# PROC051C_QSPI_Flash_Reference.net
KiCad netlist of a schematic drawn in Altium Designer
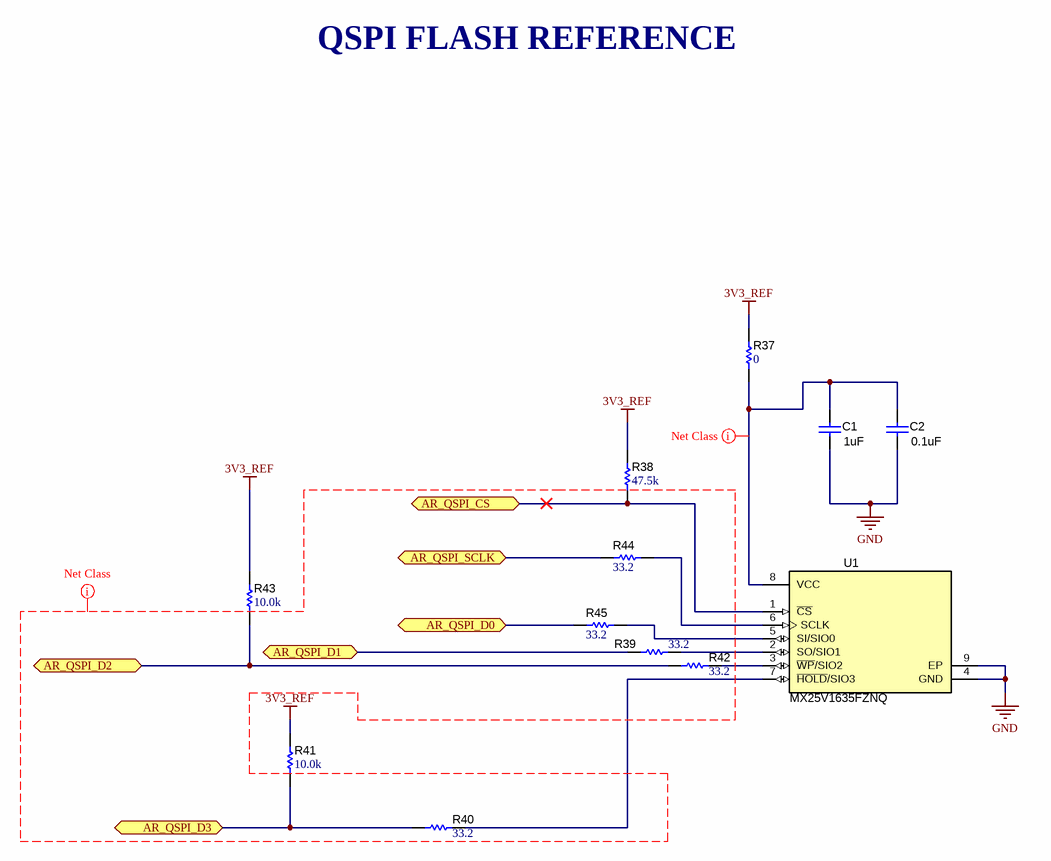
[diagram p0: PROC051C_QSPI_Flash_Reference.SchDoc]

(export (version "E")
  (design (tool "Eeschema 10.0.6"))
  (components
    (comp (ref "C1")
      (value "GCM188R71C105KA64D")
      (footprint "0603")
      (description "CAP, CERM, 1 uF, 16 V, +/- 10%, X7R, AEC-Q200 Grade 1, 0603")
      (fields
        (field (name "MANUFACTURER") "MuRata")
        (field (name "VALUEDISPLAYED") "1uF")
        (field (name "PUBLISHER") "Texas Instruments")
      )
      (libsource (lib "Altium Vault - TI") (part "Capacitor"))
    )
    (comp (ref "C2")
      (value "CGA2B3X7R1H104K050BB")
      (footprint "0402L")
      (description "CAP, CERM, 0.1 uF, 50 V, +/- 10%, X7R, AEC-Q200 Grade 1, 0402")
      (fields
        (field (name "MANUFACTURER") "TDK")
        (field (name "VALUEDISPLAYED") "0.1uF")
        (field (name "PUBLISHER") "Texas Instruments")
      )
      (libsource (lib "Altium Vault - TI") (part "Capacitor"))
    )
    (comp (ref "R37")
      (value "ERJ-2GE0R00X")
      (footprint "0402L")
      (description "RES, 0, 5%, 0.1 W, AEC-Q200 Grade 0, 0402")
      (fields (field (name "MANUFACTURER") "Panasonic") (field (name "VALUEDISPLAYED") "0"))
      (libsource (lib "Altium Vault - TI") (part "Resistor"))
    )
    (comp (ref "R38")
      (value "CRCW040247K5FKED")
      (footprint "0402L")
      (description "RES, 47.5 k, 1%, 0.063 W, AEC-Q200 Grade 0, 0402")
      (fields (field (name "MANUFACTURER") "Vishay-Dale") (field (name "VALUEDISPLAYED") "47.5k"))
      (libsource (lib "Altium Vault - TI") (part "Resistor"))
    )
    (comp (ref "R39")
      (value "CRCW020133R2FNED")
      (footprint "0201_Silk")
      (description "RES, 33.2, 1%, 0.05 W, 0201")
      (fields (field (name "MANUFACTURER") "Vishay-Dale") (field (name "VALUEDISPLAYED") "33.2"))
      (libsource (lib "Altium Vault - TI") (part "Resistor"))
    )
    (comp (ref "R40")
      (value "CRCW020133R2FNED")
      (footprint "0201_Silk")
      (description "RES, 33.2, 1%, 0.05 W, 0201")
      (fields (field (name "MANUFACTURER") "Vishay-Dale") (field (name "VALUEDISPLAYED") "33.2"))
      (libsource (lib "Altium Vault - TI") (part "Resistor"))
    )
    (comp (ref "R41")
      (value "CRCW040210K0FKED")
      (footprint "0402L")
      (description "RES, 10.0 k, 1%, 0.063 W, AEC-Q200 Grade 0, 0402")
      (fields (field (name "MANUFACTURER") "Vishay-Dale") (field (name "VALUEDISPLAYED") "10.0k"))
      (libsource (lib "Altium Vault - TI") (part "Resistor"))
    )
    (comp (ref "R42")
      (value "CRCW020133R2FNED")
      (footprint "0201_Silk")
      (description "RES, 33.2, 1%, 0.05 W, 0201")
      (fields (field (name "MANUFACTURER") "Vishay-Dale") (field (name "VALUEDISPLAYED") "33.2"))
      (libsource (lib "Altium Vault - TI") (part "Resistor"))
    )
    (comp (ref "R43")
      (value "CRCW040210K0FKED")
      (footprint "0402L")
      (description "RES, 10.0 k, 1%, 0.063 W, AEC-Q200 Grade 0, 0402")
      (fields (field (name "MANUFACTURER") "Vishay-Dale") (field (name "VALUEDISPLAYED") "10.0k"))
      (libsource (lib "Altium Vault - TI") (part "Resistor"))
    )
    (comp (ref "R44")
      (value "CRCW020133R2FNED")
      (footprint "0201_Silk")
      (description "RES, 33.2, 1%, 0.05 W, 0201")
      (fields (field (name "MANUFACTURER") "Vishay-Dale") (field (name "VALUEDISPLAYED") "33.2"))
      (libsource (lib "Altium Vault - TI") (part "CMP-0027275-3"))
    )
    (comp (ref "R45")
      (value "CRCW020133R2FNED")
      (footprint "0201_Silk")
      (description "RES, 33.2, 1%, 0.05 W, 0201")
      (fields (field (name "MANUFACTURER") "Vishay-Dale") (field (name "VALUEDISPLAYED") "33.2"))
      (libsource (lib "Altium Vault - TI") (part "Resistor"))
    )
    (comp (ref "U1")
      (value "MX25V1635FZNQ")
      (footprint "WSON-8L_6x5MM_EP")
      (description "2.3V-3.6V, 16M-BIT [x 1/x 2/x 4] CMOS FLASH Memory, WSON-8")
      (fields (field (name "MANUFACTURER") "Macronix International Co., LTD"))
      (libsource (lib "Altium Vault - TI") (part "MX25V1635FZ"))
    )
  )
  (nets
    (net (code "1") (name "/AR_QSPI_CS") (class "Default")
      (node (ref "R38") (pin "1") (pinfunction "1_1") (pintype "passive"))
      (node (ref "U1") (pin "1") (pinfunction "CS_1") (pintype "input"))
    )
    (net (code "2") (name "/AR_QSPI_D0") (class "Default")
      (node (ref "R45") (pin "2") (pinfunction "2_2") (pintype "passive"))
    )
    (net (code "3") (name "/AR_QSPI_D1") (class "Default")
      (node (ref "R39") (pin "1") (pinfunction "1_1") (pintype "passive"))
    )
    (net (code "4") (name "/AR_QSPI_D2") (class "Default")
      (node (ref "R42") (pin "1") (pinfunction "1_1") (pintype "passive"))
      (node (ref "R43") (pin "1") (pinfunction "1_1") (pintype "passive"))
    )
    (net (code "5") (name "/AR_QSPI_D3") (class "Default")
      (node (ref "R40") (pin "2") (pinfunction "2_2") (pintype "passive"))
      (node (ref "R41") (pin "1") (pinfunction "1_1") (pintype "passive"))
    )
    (net (code "6") (name "/AR_QSPI_SCLK") (class "Default")
      (node (ref "R44") (pin "2") (pinfunction "2_2") (pintype "passive"))
    )
    (net (code "7") (name "3V3_REF") (class "Default")
      (node (ref "R37") (pin "1") (pinfunction "1_1") (pintype "passive"))
      (node (ref "R38") (pin "2") (pinfunction "2_2") (pintype "passive"))
      (node (ref "R41") (pin "2") (pinfunction "2_2") (pintype "passive"))
      (node (ref "R43") (pin "2") (pinfunction "2_2") (pintype "passive"))
    )
    (net (code "8") (name "GND") (class "Default")
      (node (ref "C1") (pin "1") (pinfunction "1_1") (pintype "passive"))
      (node (ref "C2") (pin "1") (pinfunction "1_1") (pintype "passive"))
      (node (ref "U1") (pin "4") (pinfunction "GND_4") (pintype "power_in"))
      (node (ref "U1") (pin "9") (pinfunction "EP_9") (pintype "passive"))
    )
    (net (code "9") (name "Net-(U1-SCLK)") (class "Default")
      (node (ref "R44") (pin "1") (pinfunction "1_1") (pintype "passive"))
      (node (ref "U1") (pin "6") (pinfunction "SCLK_6") (pintype "input"))
    )
    (net (code "10") (name "Net-(U1-SI{slash}SIO0)") (class "Default")
      (node (ref "R45") (pin "1") (pinfunction "1_1") (pintype "passive"))
      (node (ref "U1") (pin "5") (pinfunction "SI/SIO0_5") (pintype "bidirectional"))
    )
    (net (code "11") (name "Net-(U1-SO{slash}SIO1)") (class "Default")
      (node (ref "R39") (pin "2") (pinfunction "2_2") (pintype "passive"))
      (node (ref "U1") (pin "2") (pinfunction "SO/SIO1_2") (pintype "bidirectional"))
    )
    (net (code "12") (name "Net-(U1-VCC)") (class "Default")
      (node (ref "C1") (pin "2") (pinfunction "2_2") (pintype "passive"))
      (node (ref "C2") (pin "2") (pinfunction "2_2") (pintype "passive"))
      (node (ref "R37") (pin "2") (pinfunction "2_2") (pintype "passive"))
      (node (ref "U1") (pin "8") (pinfunction "VCC_8") (pintype "power_in"))
    )
    (net (code "13") (name "Net-(U1-~{HOLD}{slash}SIO3)") (class "Default")
      (node (ref "R40") (pin "1") (pinfunction "1_1") (pintype "passive"))
      (node (ref "U1") (pin "7") (pinfunction "~{HOLD}/SIO3_7") (pintype "bidirectional"))
    )
    (net (code "14") (name "Net-(U1-~{WP}{slash}SIO2)") (class "Default")
      (node (ref "R42") (pin "2") (pinfunction "2_2") (pintype "passive"))
      (node (ref "U1") (pin "3") (pinfunction "~{WP}/SIO2_3") (pintype "bidirectional"))
    )
  )
)
